# HB_Driver1.net
KiCad netlist of a schematic drawn in Altium Designer
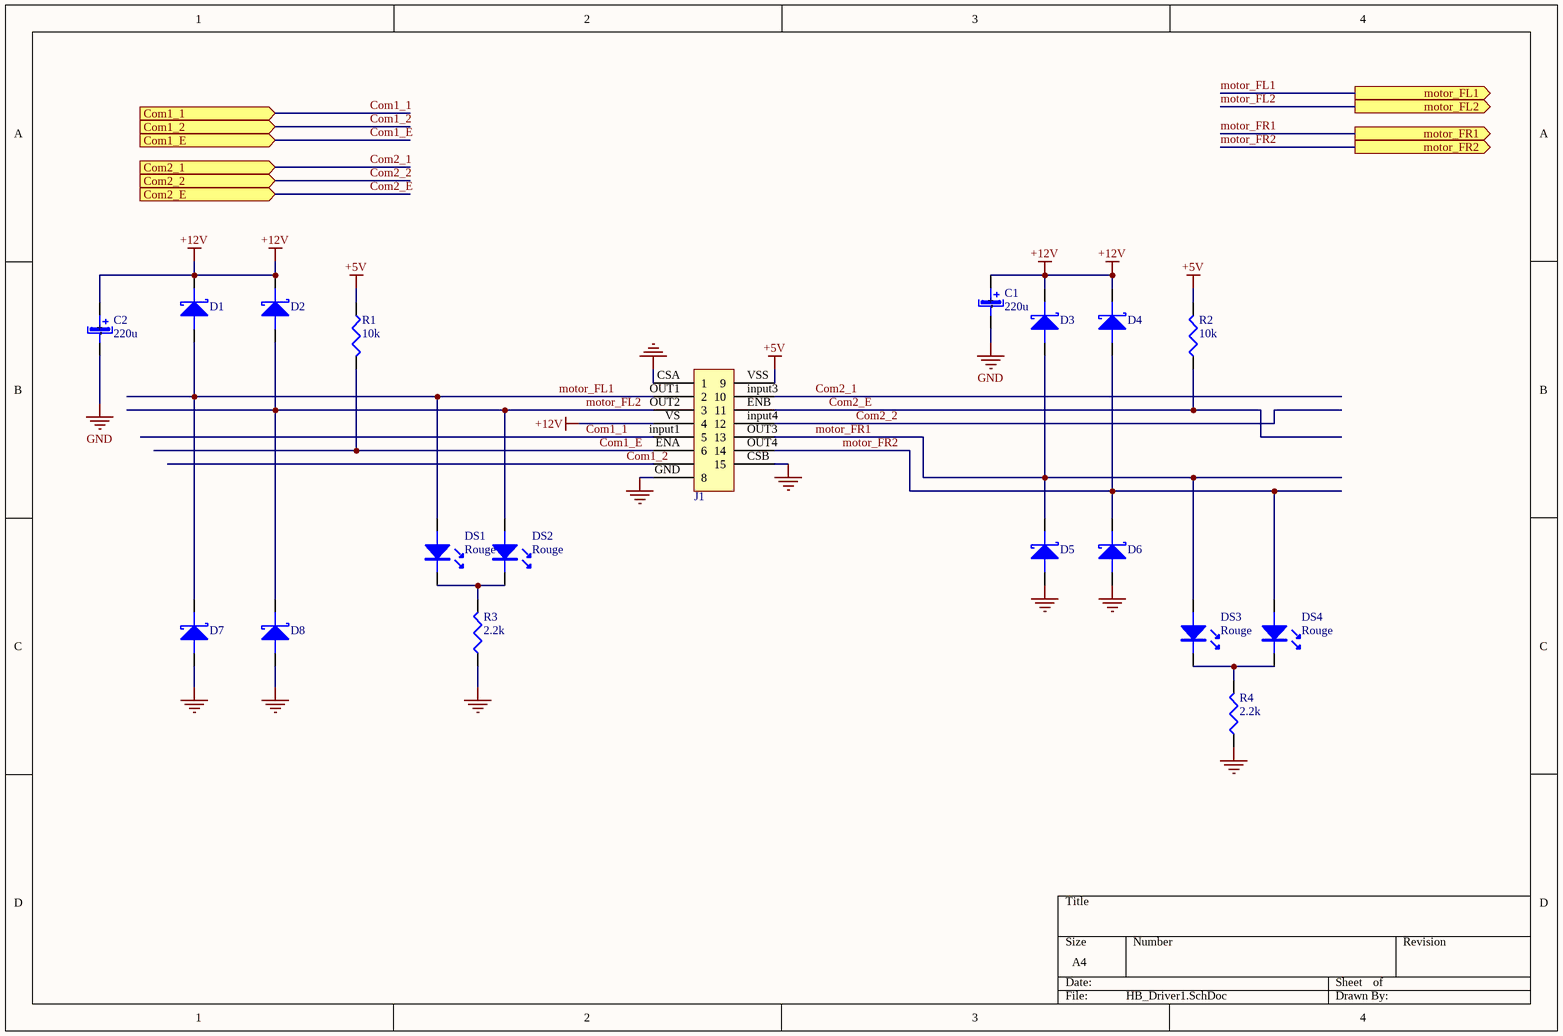
[diagram p0: HB_Driver1.SchDoc]

(export (version "E")
  (design (tool "Eeschema 10.0.6"))
  (components
    (comp (ref "C1")
      (value "220u")
      (footprint "CAPAE0810X700N")
      (description "Condensateur polatisé")
      (fields (field (name "Comment") "Cap_220u") (field (name "DESIGNER") "ECAM 2004"))
      (libsource (lib "HBLib") (part "Cap_220u"))
    )
    (comp (ref "C2")
      (value "220u")
      (footprint "CAPAE0810X700N")
      (description "Condensateur polatisé")
      (fields (field (name "Comment") "Cap_220u") (field (name "DESIGNER") "ECAM 2004"))
      (libsource (lib "HBLib") (part "Cap_220u"))
    )
    (comp (ref "D1")
      (value "Diode Schottky")
      (footprint "SOD-123")
      (fields (field (name "DESIGNER") "ECAM 2005"))
      (libsource (lib "HBLib") (part "Diode Schottky"))
    )
    (comp (ref "D2")
      (value "Diode Schottky")
      (footprint "SOD-123")
      (fields (field (name "DESIGNER") "ECAM 2005"))
      (libsource (lib "HBLib") (part "Diode Schottky"))
    )
    (comp (ref "D3")
      (value "Diode Schottky")
      (footprint "SOD-123")
      (fields (field (name "DESIGNER") "ECAM 2005"))
      (libsource (lib "HBLib") (part "Diode Schottky"))
    )
    (comp (ref "D4")
      (value "Diode Schottky")
      (footprint "SOD-123")
      (fields (field (name "DESIGNER") "ECAM 2005"))
      (libsource (lib "HBLib") (part "Diode Schottky"))
    )
    (comp (ref "D5")
      (value "Diode Schottky")
      (footprint "SOD-123")
      (fields (field (name "DESIGNER") "ECAM 2005"))
      (libsource (lib "HBLib") (part "Diode Schottky"))
    )
    (comp (ref "D6")
      (value "Diode Schottky")
      (footprint "SOD-123")
      (fields (field (name "DESIGNER") "ECAM 2005"))
      (libsource (lib "HBLib") (part "Diode Schottky"))
    )
    (comp (ref "D7")
      (value "Diode Schottky")
      (footprint "SOD-123")
      (fields (field (name "DESIGNER") "ECAM 2005"))
      (libsource (lib "HBLib") (part "Diode Schottky"))
    )
    (comp (ref "D8")
      (value "Diode Schottky")
      (footprint "SOD-123")
      (fields (field (name "DESIGNER") "ECAM 2005"))
      (libsource (lib "HBLib") (part "Diode Schottky"))
    )
    (comp (ref "DS1")
      (value "LED")
      (footprint "3.5X2.8X1.9")
      (fields (field (name "COLOR") "Rouge") (field (name "DESIGNER") "ECAM 2004"))
      (libsource (lib "HBLib") (part "LED"))
    )
    (comp (ref "DS2")
      (value "LED")
      (footprint "3.5X2.8X1.9")
      (fields (field (name "COLOR") "Rouge") (field (name "DESIGNER") "ECAM 2004"))
      (libsource (lib "HBLib") (part "LED"))
    )
    (comp (ref "DS3")
      (value "LED")
      (footprint "3.5X2.8X1.9")
      (fields (field (name "COLOR") "Rouge") (field (name "DESIGNER") "ECAM 2004"))
      (libsource (lib "HBLib") (part "LED"))
    )
    (comp (ref "DS4")
      (value "LED")
      (footprint "3.5X2.8X1.9")
      (fields (field (name "COLOR") "Rouge") (field (name "DESIGNER") "ECAM 2004"))
      (libsource (lib "HBLib") (part "LED"))
    )
    (comp (ref "J1")
      (value "L298")
      (footprint "MultiWatt15")
      (description "Connecteur")
      (fields (field (name "DESIGNER") "ECAM 2004"))
      (libsource (lib "HBLib") (part "L298"))
    )
    (comp (ref "R1")
      (value "10k")
      (footprint "6-0805_L")
      (description "Résistance standard")
      (fields (field (name "Comment") "Res_10k") (field (name "DESIGNER") "ECAM 2005"))
      (libsource (lib "HBLib") (part "Res_10k"))
    )
    (comp (ref "R2")
      (value "10k")
      (footprint "6-0805_L")
      (description "Résistance standard")
      (fields (field (name "Comment") "Res_10k") (field (name "DESIGNER") "ECAM 2005"))
      (libsource (lib "HBLib") (part "Res_10k"))
    )
    (comp (ref "R3")
      (value "2.2k")
      (footprint "6-0805_L")
      (description "Résistance standard")
      (fields (field (name "Comment") "Res_2.2k") (field (name "DESIGNER") "ECAM 2005"))
      (libsource (lib "HBLib") (part "Res_2.2k"))
    )
    (comp (ref "R4")
      (value "2.2k")
      (footprint "6-0805_L")
      (description "Résistance standard")
      (fields (field (name "Comment") "Res_2.2k") (field (name "DESIGNER") "ECAM 2005"))
      (libsource (lib "HBLib") (part "Res_2.2k"))
    )
  )
  (nets
    (net (code "1") (name "+5V") (class "Default")
      (node (ref "J1") (pin "VSS") (pinfunction "9_VSS") (pintype "passive"))
      (node (ref "R1") (pin "1") (pinfunction "1_1") (pintype "passive"))
      (node (ref "R2") (pin "2") (pinfunction "2_2") (pintype "passive"))
    )
    (net (code "2") (name "+12V") (class "Default")
      (node (ref "C1") (pin "POS") (pinfunction "+_POS") (pintype "passive"))
      (node (ref "C2") (pin "POS") (pinfunction "+_POS") (pintype "passive"))
      (node (ref "D1") (pin "1") (pinfunction "K_1") (pintype "passive"))
      (node (ref "D2") (pin "1") (pinfunction "K_1") (pintype "passive"))
      (node (ref "D3") (pin "1") (pinfunction "K_1") (pintype "passive"))
      (node (ref "D4") (pin "1") (pinfunction "K_1") (pintype "passive"))
      (node (ref "J1") (pin "VS") (pinfunction "4_VS") (pintype "passive"))
    )
    (net (code "3") (name "/Com1_1") (class "Default")
      (node (ref "J1") (pin "input1") (pinfunction "5_input1") (pintype "passive"))
    )
    (net (code "4") (name "/Com1_2") (class "Default")
      (node (ref "J1") (pin "input2") (pinfunction "7_input2") (pintype "passive"))
    )
    (net (code "5") (name "/Com1_E") (class "Default")
      (node (ref "J1") (pin "ENA") (pinfunction "6_ENA") (pintype "passive"))
      (node (ref "R1") (pin "2") (pinfunction "2_2") (pintype "passive"))
    )
    (net (code "6") (name "/Com2_1") (class "Default")
      (node (ref "J1") (pin "input3") (pinfunction "10_input3") (pintype "passive"))
    )
    (net (code "7") (name "/Com2_2") (class "Default")
      (node (ref "J1") (pin "input4") (pinfunction "12_input4") (pintype "passive"))
    )
    (net (code "8") (name "/Com2_E") (class "Default")
      (node (ref "J1") (pin "ENB") (pinfunction "11_ENB") (pintype "passive"))
      (node (ref "R2") (pin "1") (pinfunction "1_1") (pintype "passive"))
    )
    (net (code "9") (name "/motor_FL1") (class "Default")
      (node (ref "D1") (pin "2") (pinfunction "A_2") (pintype "passive"))
      (node (ref "D7") (pin "1") (pinfunction "K_1") (pintype "passive"))
      (node (ref "DS1") (pin "1") (pinfunction "A_1") (pintype "passive"))
      (node (ref "J1") (pin "OUT1") (pinfunction "2_OUT1") (pintype "passive"))
    )
    (net (code "10") (name "/motor_FL2") (class "Default")
      (node (ref "D2") (pin "2") (pinfunction "A_2") (pintype "passive"))
      (node (ref "D8") (pin "1") (pinfunction "K_1") (pintype "passive"))
      (node (ref "DS2") (pin "1") (pinfunction "A_1") (pintype "passive"))
      (node (ref "J1") (pin "OUT2") (pinfunction "3_OUT2") (pintype "passive"))
    )
    (net (code "11") (name "/motor_FR1") (class "Default")
      (node (ref "D3") (pin "2") (pinfunction "A_2") (pintype "passive"))
      (node (ref "D5") (pin "1") (pinfunction "K_1") (pintype "passive"))
      (node (ref "DS3") (pin "1") (pinfunction "A_1") (pintype "passive"))
      (node (ref "J1") (pin "OUT3") (pinfunction "13_OUT3") (pintype "passive"))
    )
    (net (code "12") (name "/motor_FR2") (class "Default")
      (node (ref "D4") (pin "2") (pinfunction "A_2") (pintype "passive"))
      (node (ref "D6") (pin "1") (pinfunction "K_1") (pintype "passive"))
      (node (ref "DS4") (pin "1") (pinfunction "A_1") (pintype "passive"))
      (node (ref "J1") (pin "OUT4") (pinfunction "14_OUT4") (pintype "passive"))
    )
    (net (code "13") (name "GND") (class "Default")
      (node (ref "C1") (pin "NEG") (pinfunction "-_NEG") (pintype "passive"))
      (node (ref "C2") (pin "NEG") (pinfunction "-_NEG") (pintype "passive"))
      (node (ref "D5") (pin "2") (pinfunction "A_2") (pintype "passive"))
      (node (ref "D6") (pin "2") (pinfunction "A_2") (pintype "passive"))
      (node (ref "D7") (pin "2") (pinfunction "A_2") (pintype "passive"))
      (node (ref "D8") (pin "2") (pinfunction "A_2") (pintype "passive"))
      (node (ref "J1") (pin "CSA") (pinfunction "1_CSA") (pintype "passive"))
      (node (ref "J1") (pin "CSB") (pinfunction "15_CSB") (pintype "passive"))
      (node (ref "J1") (pin "GND") (pinfunction "8_GND") (pintype "passive"))
      (node (ref "R3") (pin "1") (pinfunction "1_1") (pintype "passive"))
      (node (ref "R4") (pin "1") (pinfunction "1_1") (pintype "passive"))
    )
    (net (code "14") (name "Net-(DS1-K)") (class "Default")
      (node (ref "DS1") (pin "2") (pinfunction "K_2") (pintype "passive"))
      (node (ref "DS2") (pin "2") (pinfunction "K_2") (pintype "passive"))
      (node (ref "R3") (pin "2") (pinfunction "2_2") (pintype "passive"))
    )
    (net (code "15") (name "Net-(DS3-K)") (class "Default")
      (node (ref "DS3") (pin "2") (pinfunction "K_2") (pintype "passive"))
      (node (ref "DS4") (pin "2") (pinfunction "K_2") (pintype "passive"))
      (node (ref "R4") (pin "2") (pinfunction "2_2") (pintype "passive"))
    )
  )
)
